# tft-touch.net
KiCad netlist of a schematic drawn in EAGLE
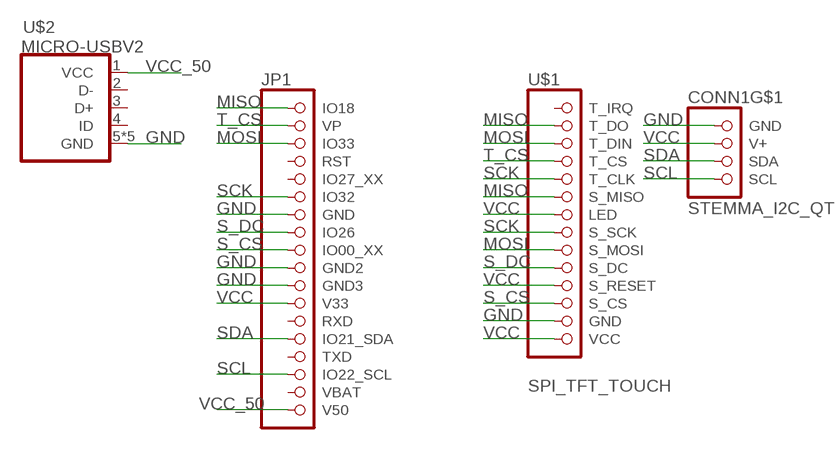
[diagram p0: schematic, sheet 1]

(export (version "E")
  (design (tool "Eeschema 10.0.6"))
  (components
    (comp (ref "CONN1")
      (value "STEMMA_I2C_QT")
      (footprint "eagle-import:JST_SH4")
      (libsource (lib "eagle-import") (part "STEMMA_I2C_QT"))
    )
    (comp (ref "JP1")
      (value "TTGO-TS-ESP32")
      (footprint "eagle-import:00_2X9")
      (libsource (lib "eagle-import") (part "TTGO-TS-ESP32"))
    )
    (comp (ref "U$1")
      (value "SPI_TFT_TOUCH")
      (footprint "eagle-import:1X14_ROUND_70")
      (libsource (lib "eagle-import") (part "SPI_TFT_TOUCH"))
    )
    (comp (ref "U$2")
      (value "MICRO-USBV2")
      (footprint "eagle-import:MICRO-USB-2")
      (libsource (lib "eagle-import") (part "MICRO-USBV2"))
    )
  )
  (nets
    (net (code "1") (name "/GND") (class "Default")
      (node (ref "CONN1") (pin "1") (pinfunction "GND_1") (pintype "passive"))
      (node (ref "JP1") (pin "10") (pinfunction "GND2_10") (pintype "power_in"))
      (node (ref "JP1") (pin "11") (pinfunction "GND3_11") (pintype "power_in"))
      (node (ref "JP1") (pin "7") (pinfunction "GND_7") (pintype "power_in"))
      (node (ref "U$1") (pin "13") (pinfunction "GND_13") (pintype "passive"))
      (node (ref "U$2") (pin "5") (pinfunction "GND_5") (pintype "power_in"))
      (node (ref "U$2") (pin "P$1") (pinfunction "GND_P$1") (pintype "power_in"))
      (node (ref "U$2") (pin "P$2") (pinfunction "GND_P$2") (pintype "power_in"))
      (node (ref "U$2") (pin "P$3") (pinfunction "GND_P$3") (pintype "power_in"))
      (node (ref "U$2") (pin "P$4") (pinfunction "GND_P$4") (pintype "power_in"))
    )
    (net (code "2") (name "/MISO") (class "Default")
      (node (ref "JP1") (pin "1") (pinfunction "IO18_1") (pintype "passive"))
      (node (ref "U$1") (pin "2") (pinfunction "T_DO_2") (pintype "passive"))
      (node (ref "U$1") (pin "6") (pinfunction "S_MISO_6") (pintype "passive"))
    )
    (net (code "3") (name "/MOSI") (class "Default")
      (node (ref "JP1") (pin "3") (pinfunction "IO33_3") (pintype "passive"))
      (node (ref "U$1") (pin "3") (pinfunction "T_DIN_3") (pintype "passive"))
      (node (ref "U$1") (pin "9") (pinfunction "S_MOSI_9") (pintype "passive"))
    )
    (net (code "4") (name "/SCK") (class "Default")
      (node (ref "JP1") (pin "6") (pinfunction "IO32_6") (pintype "passive"))
      (node (ref "U$1") (pin "5") (pinfunction "T_CLK_5") (pintype "passive"))
      (node (ref "U$1") (pin "8") (pinfunction "S_SCK_8") (pintype "passive"))
    )
    (net (code "5") (name "/SCL") (class "Default")
      (node (ref "CONN1") (pin "4") (pinfunction "SCL_4") (pintype "passive"))
      (node (ref "JP1") (pin "16") (pinfunction "IO22_SCL_16") (pintype "passive"))
    )
    (net (code "6") (name "/SDA") (class "Default")
      (node (ref "CONN1") (pin "3") (pinfunction "SDA_3") (pintype "passive"))
      (node (ref "JP1") (pin "14") (pinfunction "IO21_SDA_14") (pintype "passive"))
    )
    (net (code "7") (name "/S_CS") (class "Default")
      (node (ref "JP1") (pin "9") (pinfunction "IO00_XX_9") (pintype "passive"))
      (node (ref "U$1") (pin "12") (pinfunction "S_CS_12") (pintype "passive"))
    )
    (net (code "8") (name "/S_DC") (class "Default")
      (node (ref "JP1") (pin "8") (pinfunction "IO26_8") (pintype "passive"))
      (node (ref "U$1") (pin "10") (pinfunction "S_DC_10") (pintype "passive"))
    )
    (net (code "9") (name "/T_CS") (class "Default")
      (node (ref "JP1") (pin "2") (pinfunction "VP_2") (pintype "passive"))
      (node (ref "U$1") (pin "4") (pinfunction "T_CS_4") (pintype "passive"))
    )
    (net (code "10") (name "/VCC") (class "Default")
      (node (ref "CONN1") (pin "2") (pinfunction "V+_2") (pintype "passive"))
      (node (ref "JP1") (pin "12") (pinfunction "V33_12") (pintype "passive"))
      (node (ref "U$1") (pin "11") (pinfunction "S_RESET_11") (pintype "passive"))
      (node (ref "U$1") (pin "14") (pinfunction "VCC_14") (pintype "passive"))
      (node (ref "U$1") (pin "7") (pinfunction "LED_7") (pintype "passive"))
    )
    (net (code "11") (name "/VCC_50") (class "Default")
      (node (ref "JP1") (pin "18") (pinfunction "V50_18") (pintype "power_in"))
      (node (ref "U$2") (pin "1") (pinfunction "VCC_1") (pintype "power_in"))
    )
    (net (code "12") (name "unconnected-(JP1-IO27_XX-Pad5)") (class "Default")
      (node (ref "JP1") (pin "5") (pinfunction "IO27_XX_5") (pintype "passive"))
    )
    (net (code "13") (name "unconnected-(JP1-RST-Pad4)") (class "Default")
      (node (ref "JP1") (pin "4") (pinfunction "RST_4") (pintype "passive"))
    )
    (net (code "14") (name "unconnected-(JP1-RXD-Pad13)") (class "Default")
      (node (ref "JP1") (pin "13") (pinfunction "RXD_13") (pintype "passive"))
    )
    (net (code "15") (name "unconnected-(JP1-TXD-Pad15)") (class "Default")
      (node (ref "JP1") (pin "15") (pinfunction "TXD_15") (pintype "passive"))
    )
    (net (code "16") (name "unconnected-(JP1-VBAT-Pad17)") (class "Default")
      (node (ref "JP1") (pin "17") (pinfunction "VBAT_17") (pintype "passive"))
    )
    (net (code "17") (name "unconnected-(U$1-T_IRQ-Pad1)") (class "Default")
      (node (ref "U$1") (pin "1") (pinfunction "T_IRQ_1") (pintype "passive"))
    )
    (net (code "18") (name "unconnected-(U$2-D+-Pad3)") (class "Default")
      (node (ref "U$2") (pin "3") (pinfunction "D+_3") (pintype "bidirectional"))
    )
    (net (code "19") (name "unconnected-(U$2-D--Pad2)") (class "Default")
      (node (ref "U$2") (pin "2") (pinfunction "D-_2") (pintype "bidirectional"))
    )
    (net (code "20") (name "unconnected-(U$2-ID-Pad4)") (class "Default")
      (node (ref "U$2") (pin "4") (pinfunction "ID_4") (pintype "bidirectional"))
    )
  )
)
